# Vjtronics.net
KiCad netlist of a schematic drawn in EAGLE
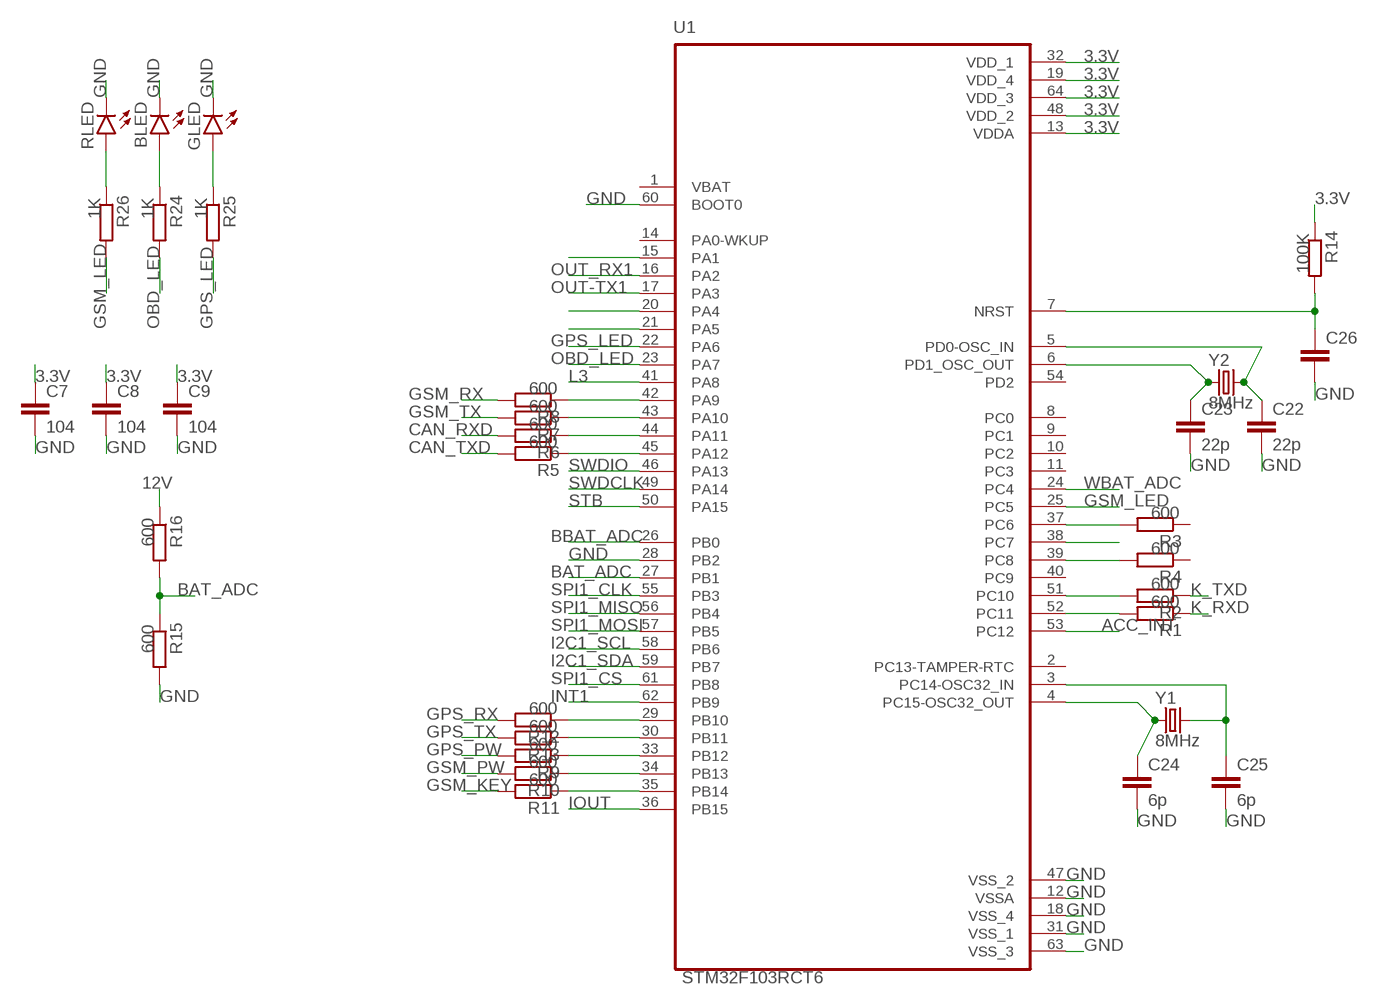
[diagram p0: schematic, sheet 1]

(export (version "E")
  (design (tool "Eeschema 10.0.6"))
  (components
    (comp (ref "BLED")
      (value "LEDCHIPLED_0805")
      (footprint "eagle-import:CHIPLED_0805")
      (libsource (lib "eagle-import") (part "LEDCHIPLED_0805"))
    )
    (comp (ref "C7")
      (value "104")
      (footprint "eagle-import:C0805")
      (libsource (lib "eagle-import") (part "C-EUC0805"))
    )
    (comp (ref "C8")
      (value "104")
      (footprint "eagle-import:C0805")
      (libsource (lib "eagle-import") (part "C-EUC0805"))
    )
    (comp (ref "C9")
      (value "104")
      (footprint "eagle-import:C0805")
      (libsource (lib "eagle-import") (part "C-EUC0805"))
    )
    (comp (ref "C22")
      (value "22p")
      (footprint "eagle-import:C0805")
      (libsource (lib "eagle-import") (part "C-EUC0805"))
    )
    (comp (ref "C23")
      (value "22p")
      (footprint "eagle-import:C0805")
      (libsource (lib "eagle-import") (part "C-EUC0805"))
    )
    (comp (ref "C24")
      (value "6p")
      (footprint "eagle-import:C0805")
      (libsource (lib "eagle-import") (part "C-EUC0805"))
    )
    (comp (ref "C25")
      (value "6p")
      (footprint "eagle-import:C0805")
      (libsource (lib "eagle-import") (part "C-EUC0805"))
    )
    (comp (ref "C26")
      (value "C-EUC0805")
      (footprint "eagle-import:C0805")
      (libsource (lib "eagle-import") (part "C-EUC0805"))
    )
    (comp (ref "GLED")
      (value "LEDCHIPLED_0805")
      (footprint "eagle-import:CHIPLED_0805")
      (libsource (lib "eagle-import") (part "LEDCHIPLED_0805"))
    )
    (comp (ref "R1")
      (value "600")
      (footprint "eagle-import:M0805")
      (libsource (lib "eagle-import") (part "R-EU_M0805"))
    )
    (comp (ref "R2")
      (value "600")
      (footprint "eagle-import:M0805")
      (libsource (lib "eagle-import") (part "R-EU_M0805"))
    )
    (comp (ref "R3")
      (value "600")
      (footprint "eagle-import:M0805")
      (libsource (lib "eagle-import") (part "R-EU_M0805"))
    )
    (comp (ref "R4")
      (value "600")
      (footprint "eagle-import:M0805")
      (libsource (lib "eagle-import") (part "R-EU_M0805"))
    )
    (comp (ref "R5")
      (value "600")
      (footprint "eagle-import:M0805")
      (libsource (lib "eagle-import") (part "R-EU_M0805"))
    )
    (comp (ref "R6")
      (value "600")
      (footprint "eagle-import:M0805")
      (libsource (lib "eagle-import") (part "R-EU_M0805"))
    )
    (comp (ref "R7")
      (value "600")
      (footprint "eagle-import:M0805")
      (libsource (lib "eagle-import") (part "R-EU_M0805"))
    )
    (comp (ref "R8")
      (value "600")
      (footprint "eagle-import:M0805")
      (libsource (lib "eagle-import") (part "R-EU_M0805"))
    )
    (comp (ref "R9")
      (value "600")
      (footprint "eagle-import:M0805")
      (libsource (lib "eagle-import") (part "R-EU_M0805"))
    )
    (comp (ref "R10")
      (value "600")
      (footprint "eagle-import:M0805")
      (libsource (lib "eagle-import") (part "R-EU_M0805"))
    )
    (comp (ref "R11")
      (value "600")
      (footprint "eagle-import:M0805")
      (libsource (lib "eagle-import") (part "R-EU_M0805"))
    )
    (comp (ref "R12")
      (value "600")
      (footprint "eagle-import:M0805")
      (libsource (lib "eagle-import") (part "R-EU_M0805"))
    )
    (comp (ref "R13")
      (value "600")
      (footprint "eagle-import:M0805")
      (libsource (lib "eagle-import") (part "R-EU_M0805"))
    )
    (comp (ref "R14")
      (value "100K")
      (footprint "eagle-import:M0805")
      (libsource (lib "eagle-import") (part "R-EU_M0805"))
    )
    (comp (ref "R15")
      (value "600")
      (footprint "eagle-import:M0805")
      (libsource (lib "eagle-import") (part "R-EU_M0805"))
    )
    (comp (ref "R16")
      (value "600")
      (footprint "eagle-import:M0805")
      (libsource (lib "eagle-import") (part "R-EU_M0805"))
    )
    (comp (ref "R24")
      (value "1K")
      (footprint "eagle-import:M0805")
      (libsource (lib "eagle-import") (part "R-EU_M0805"))
    )
    (comp (ref "R25")
      (value "1K")
      (footprint "eagle-import:M0805")
      (libsource (lib "eagle-import") (part "R-EU_M0805"))
    )
    (comp (ref "R26")
      (value "1K")
      (footprint "eagle-import:M0805")
      (libsource (lib "eagle-import") (part "R-EU_M0805"))
    )
    (comp (ref "RLED")
      (value "LEDCHIPLED_0805")
      (footprint "eagle-import:CHIPLED_0805")
      (libsource (lib "eagle-import") (part "LEDCHIPLED_0805"))
    )
    (comp (ref "U1")
      (value "STM32F103RCT6")
      (footprint "eagle-import:QFP50P1200X1200X160-64N")
      (fields (field (name "MF") "STMicroelectronics"))
      (libsource (lib "eagle-import") (part "STM32F103RCT6"))
    )
    (comp (ref "Y1")
      (value "8MHz")
      (footprint "eagle-import:CSM-7X-DU")
      (libsource (lib "eagle-import") (part "CSM-7X-DU"))
    )
    (comp (ref "Y2")
      (value "8MHz")
      (footprint "eagle-import:CSM-7X-DU")
      (libsource (lib "eagle-import") (part "CSM-7X-DU"))
    )
  )
  (nets
    (net (code "1") (name "/3.3V") (class "Default")
      (node (ref "C7") (pin "1") (pinfunction "1_1") (pintype "passive"))
      (node (ref "C8") (pin "1") (pinfunction "1_1") (pintype "passive"))
      (node (ref "C9") (pin "1") (pinfunction "1_1") (pintype "passive"))
      (node (ref "R14") (pin "1") (pinfunction "1_1") (pintype "passive"))
      (node (ref "U1") (pin "13") (pinfunction "VDDA_13") (pintype "power_in"))
      (node (ref "U1") (pin "19") (pinfunction "VDD_4_19") (pintype "power_in"))
      (node (ref "U1") (pin "32") (pinfunction "VDD_1_32") (pintype "power_in"))
      (node (ref "U1") (pin "48") (pinfunction "VDD_2_48") (pintype "power_in"))
      (node (ref "U1") (pin "64") (pinfunction "VDD_3_64") (pintype "power_in"))
    )
    (net (code "2") (name "/12V") (class "Default")
      (node (ref "R16") (pin "1") (pinfunction "1_1") (pintype "passive"))
    )
    (net (code "3") (name "/ACC_INT") (class "Default")
      (node (ref "U1") (pin "53") (pinfunction "PC12_53") (pintype "bidirectional"))
    )
    (net (code "4") (name "/BAT_ADC") (class "Default")
      (node (ref "R15") (pin "1") (pinfunction "1_1") (pintype "passive"))
      (node (ref "R16") (pin "2") (pinfunction "2_2") (pintype "passive"))
      (node (ref "U1") (pin "27") (pinfunction "PB1_27") (pintype "bidirectional"))
    )
    (net (code "5") (name "/BBAT_ADC") (class "Default")
      (node (ref "U1") (pin "26") (pinfunction "PB0_26") (pintype "bidirectional"))
    )
    (net (code "6") (name "/CAN_RXD") (class "Default")
      (node (ref "R6") (pin "2") (pinfunction "2_2") (pintype "passive"))
    )
    (net (code "7") (name "/CAN_TXD") (class "Default")
      (node (ref "R5") (pin "2") (pinfunction "2_2") (pintype "passive"))
    )
    (net (code "8") (name "/GND") (class "Default")
      (node (ref "BLED") (pin "C") (pinfunction "C_C") (pintype "passive"))
      (node (ref "C22") (pin "2") (pinfunction "2_2") (pintype "passive"))
      (node (ref "C23") (pin "2") (pinfunction "2_2") (pintype "passive"))
      (node (ref "C24") (pin "2") (pinfunction "2_2") (pintype "passive"))
      (node (ref "C25") (pin "2") (pinfunction "2_2") (pintype "passive"))
      (node (ref "C26") (pin "2") (pinfunction "2_2") (pintype "passive"))
      (node (ref "C7") (pin "2") (pinfunction "2_2") (pintype "passive"))
      (node (ref "C8") (pin "2") (pinfunction "2_2") (pintype "passive"))
      (node (ref "C9") (pin "2") (pinfunction "2_2") (pintype "passive"))
      (node (ref "GLED") (pin "C") (pinfunction "C_C") (pintype "passive"))
      (node (ref "R15") (pin "2") (pinfunction "2_2") (pintype "passive"))
      (node (ref "RLED") (pin "C") (pinfunction "C_C") (pintype "passive"))
      (node (ref "U1") (pin "12") (pinfunction "VSSA_12") (pintype "power_in"))
      (node (ref "U1") (pin "18") (pinfunction "VSS_4_18") (pintype "power_in"))
      (node (ref "U1") (pin "28") (pinfunction "PB2_28") (pintype "bidirectional"))
      (node (ref "U1") (pin "31") (pinfunction "VSS_1_31") (pintype "power_in"))
      (node (ref "U1") (pin "47") (pinfunction "VSS_2_47") (pintype "power_in"))
      (node (ref "U1") (pin "60") (pinfunction "BOOT0_60") (pintype "input"))
      (node (ref "U1") (pin "63") (pinfunction "VSS_3_63") (pintype "power_in"))
    )
    (net (code "9") (name "/GPS_LED") (class "Default")
      (node (ref "R25") (pin "2") (pinfunction "2_2") (pintype "passive"))
      (node (ref "U1") (pin "22") (pinfunction "PA6_22") (pintype "bidirectional"))
    )
    (net (code "10") (name "/GPS_PW") (class "Default")
      (node (ref "R9") (pin "2") (pinfunction "2_2") (pintype "passive"))
    )
    (net (code "11") (name "/GPS_RX") (class "Default")
      (node (ref "R12") (pin "2") (pinfunction "2_2") (pintype "passive"))
    )
    (net (code "12") (name "/GPS_TX") (class "Default")
      (node (ref "R13") (pin "2") (pinfunction "2_2") (pintype "passive"))
    )
    (net (code "13") (name "/GSM_KEY") (class "Default")
      (node (ref "R11") (pin "2") (pinfunction "2_2") (pintype "passive"))
    )
    (net (code "14") (name "/GSM_LED") (class "Default")
      (node (ref "R26") (pin "2") (pinfunction "2_2") (pintype "passive"))
      (node (ref "U1") (pin "25") (pinfunction "PC5_25") (pintype "bidirectional"))
    )
    (net (code "15") (name "/GSM_PW") (class "Default")
      (node (ref "R10") (pin "2") (pinfunction "2_2") (pintype "passive"))
    )
    (net (code "16") (name "/GSM_RX") (class "Default")
      (node (ref "R8") (pin "2") (pinfunction "2_2") (pintype "passive"))
    )
    (net (code "17") (name "/GSM_TX") (class "Default")
      (node (ref "R7") (pin "2") (pinfunction "2_2") (pintype "passive"))
    )
    (net (code "18") (name "/I2C1_SCL") (class "Default")
      (node (ref "U1") (pin "58") (pinfunction "PB6_58") (pintype "bidirectional"))
    )
    (net (code "19") (name "/I2C1_SDA") (class "Default")
      (node (ref "U1") (pin "59") (pinfunction "PB7_59") (pintype "bidirectional"))
    )
    (net (code "20") (name "/INT1") (class "Default")
      (node (ref "U1") (pin "62") (pinfunction "PB9_62") (pintype "bidirectional"))
    )
    (net (code "21") (name "/IOUT") (class "Default")
      (node (ref "U1") (pin "36") (pinfunction "PB15_36") (pintype "bidirectional"))
    )
    (net (code "22") (name "/K_RXD") (class "Default")
      (node (ref "R1") (pin "1") (pinfunction "1_1") (pintype "passive"))
    )
    (net (code "23") (name "/K_TXD") (class "Default")
      (node (ref "R2") (pin "1") (pinfunction "1_1") (pintype "passive"))
    )
    (net (code "24") (name "/L3") (class "Default")
      (node (ref "U1") (pin "41") (pinfunction "PA8_41") (pintype "bidirectional"))
    )
    (net (code "25") (name "/OBD_LED") (class "Default")
      (node (ref "R24") (pin "2") (pinfunction "2_2") (pintype "passive"))
      (node (ref "U1") (pin "23") (pinfunction "PA7_23") (pintype "bidirectional"))
    )
    (net (code "26") (name "/OUT-TX1") (class "Default")
      (node (ref "U1") (pin "17") (pinfunction "PA3_17") (pintype "bidirectional"))
    )
    (net (code "27") (name "/OUT_RX1") (class "Default")
      (node (ref "U1") (pin "16") (pinfunction "PA2_16") (pintype "bidirectional"))
    )
    (net (code "28") (name "/SPI1_CLK") (class "Default")
      (node (ref "U1") (pin "55") (pinfunction "PB3_55") (pintype "bidirectional"))
    )
    (net (code "29") (name "/SPI1_CS") (class "Default")
      (node (ref "U1") (pin "61") (pinfunction "PB8_61") (pintype "bidirectional"))
    )
    (net (code "30") (name "/SPI1_MISO") (class "Default")
      (node (ref "U1") (pin "56") (pinfunction "PB4_56") (pintype "bidirectional"))
    )
    (net (code "31") (name "/SPI1_MOSI") (class "Default")
      (node (ref "U1") (pin "57") (pinfunction "PB5_57") (pintype "bidirectional"))
    )
    (net (code "32") (name "/STB") (class "Default")
      (node (ref "U1") (pin "50") (pinfunction "PA15_50") (pintype "bidirectional"))
    )
    (net (code "33") (name "/SWDCLK") (class "Default")
      (node (ref "U1") (pin "49") (pinfunction "PA14_49") (pintype "bidirectional"))
    )
    (net (code "34") (name "/SWDIO") (class "Default")
      (node (ref "U1") (pin "46") (pinfunction "PA13_46") (pintype "bidirectional"))
    )
    (net (code "35") (name "/WBAT_ADC") (class "Default")
      (node (ref "U1") (pin "24") (pinfunction "PC4_24") (pintype "bidirectional"))
    )
    (net (code "36") (name "Net-(BLED-PadA)") (class "Default")
      (node (ref "BLED") (pin "A") (pinfunction "A_A") (pintype "passive"))
      (node (ref "R24") (pin "1") (pinfunction "1_1") (pintype "passive"))
    )
    (net (code "37") (name "Net-(GLED-PadA)") (class "Default")
      (node (ref "GLED") (pin "A") (pinfunction "A_A") (pintype "passive"))
      (node (ref "R25") (pin "1") (pinfunction "1_1") (pintype "passive"))
    )
    (net (code "38") (name "Net-(R26-Pad1)") (class "Default")
      (node (ref "R26") (pin "1") (pinfunction "1_1") (pintype "passive"))
      (node (ref "RLED") (pin "A") (pinfunction "A_A") (pintype "passive"))
    )
    (net (code "39") (name "Net-(U1-NRST)") (class "Default")
      (node (ref "C26") (pin "1") (pinfunction "1_1") (pintype "passive"))
      (node (ref "R14") (pin "2") (pinfunction "2_2") (pintype "passive"))
      (node (ref "U1") (pin "7") (pinfunction "NRST_7") (pintype "input"))
    )
    (net (code "40") (name "Net-(U1-PA9)") (class "Default")
      (node (ref "R8") (pin "1") (pinfunction "1_1") (pintype "passive"))
      (node (ref "U1") (pin "42") (pinfunction "PA9_42") (pintype "bidirectional"))
    )
    (net (code "41") (name "Net-(U1-PA10)") (class "Default")
      (node (ref "R7") (pin "1") (pinfunction "1_1") (pintype "passive"))
      (node (ref "U1") (pin "43") (pinfunction "PA10_43") (pintype "bidirectional"))
    )
    (net (code "42") (name "Net-(U1-PA11)") (class "Default")
      (node (ref "R6") (pin "1") (pinfunction "1_1") (pintype "passive"))
      (node (ref "U1") (pin "44") (pinfunction "PA11_44") (pintype "bidirectional"))
    )
    (net (code "43") (name "Net-(U1-PA12)") (class "Default")
      (node (ref "R5") (pin "1") (pinfunction "1_1") (pintype "passive"))
      (node (ref "U1") (pin "45") (pinfunction "PA12_45") (pintype "bidirectional"))
    )
    (net (code "44") (name "Net-(U1-PB10)") (class "Default")
      (node (ref "R12") (pin "1") (pinfunction "1_1") (pintype "passive"))
      (node (ref "U1") (pin "29") (pinfunction "PB10_29") (pintype "bidirectional"))
    )
    (net (code "45") (name "Net-(U1-PB11)") (class "Default")
      (node (ref "R13") (pin "1") (pinfunction "1_1") (pintype "passive"))
      (node (ref "U1") (pin "30") (pinfunction "PB11_30") (pintype "bidirectional"))
    )
    (net (code "46") (name "Net-(U1-PB12)") (class "Default")
      (node (ref "R9") (pin "1") (pinfunction "1_1") (pintype "passive"))
      (node (ref "U1") (pin "33") (pinfunction "PB12_33") (pintype "bidirectional"))
    )
    (net (code "47") (name "Net-(U1-PB13)") (class "Default")
      (node (ref "R10") (pin "1") (pinfunction "1_1") (pintype "passive"))
      (node (ref "U1") (pin "34") (pinfunction "PB13_34") (pintype "bidirectional"))
    )
    (net (code "48") (name "Net-(U1-PB14)") (class "Default")
      (node (ref "R11") (pin "1") (pinfunction "1_1") (pintype "passive"))
      (node (ref "U1") (pin "35") (pinfunction "PB14_35") (pintype "bidirectional"))
    )
    (net (code "49") (name "Net-(U1-PC6)") (class "Default")
      (node (ref "R3") (pin "2") (pinfunction "2_2") (pintype "passive"))
      (node (ref "U1") (pin "37") (pinfunction "PC6_37") (pintype "bidirectional"))
    )
    (net (code "50") (name "Net-(U1-PC8)") (class "Default")
      (node (ref "R4") (pin "2") (pinfunction "2_2") (pintype "passive"))
      (node (ref "U1") (pin "39") (pinfunction "PC8_39") (pintype "bidirectional"))
    )
    (net (code "51") (name "Net-(U1-PC10)") (class "Default")
      (node (ref "R2") (pin "2") (pinfunction "2_2") (pintype "passive"))
      (node (ref "U1") (pin "51") (pinfunction "PC10_51") (pintype "bidirectional"))
    )
    (net (code "52") (name "Net-(U1-PC11)") (class "Default")
      (node (ref "R1") (pin "2") (pinfunction "2_2") (pintype "passive"))
      (node (ref "U1") (pin "52") (pinfunction "PC11_52") (pintype "bidirectional"))
    )
    (net (code "53") (name "Net-(U1-PC14-OSC32_IN)") (class "Default")
      (node (ref "C25") (pin "1") (pinfunction "1_1") (pintype "passive"))
      (node (ref "U1") (pin "3") (pinfunction "PC14-OSC32_IN_3") (pintype "bidirectional"))
      (node (ref "Y1") (pin "2") (pinfunction "2_2") (pintype "passive"))
    )
    (net (code "54") (name "Net-(U1-PC15-OSC32_OUT)") (class "Default")
      (node (ref "C24") (pin "1") (pinfunction "1_1") (pintype "passive"))
      (node (ref "U1") (pin "4") (pinfunction "PC15-OSC32_OUT_4") (pintype "bidirectional"))
      (node (ref "Y1") (pin "1") (pinfunction "1_1") (pintype "passive"))
    )
    (net (code "55") (name "Net-(U1-PD0-OSC_IN)") (class "Default")
      (node (ref "C22") (pin "1") (pinfunction "1_1") (pintype "passive"))
      (node (ref "U1") (pin "5") (pinfunction "PD0-OSC_IN_5") (pintype "input"))
      (node (ref "Y2") (pin "2") (pinfunction "2_2") (pintype "passive"))
    )
    (net (code "56") (name "Net-(U1-PD1_OSC_OUT)") (class "Default")
      (node (ref "C23") (pin "1") (pinfunction "1_1") (pintype "passive"))
      (node (ref "U1") (pin "6") (pinfunction "PD1_OSC_OUT_6") (pintype "output"))
      (node (ref "Y2") (pin "1") (pinfunction "1_1") (pintype "passive"))
    )
    (net (code "57") (name "unconnected-(R3-Pad1)") (class "Default")
      (node (ref "R3") (pin "1") (pinfunction "1_1") (pintype "passive"))
    )
    (net (code "58") (name "unconnected-(R4-Pad1)") (class "Default")
      (node (ref "R4") (pin "1") (pinfunction "1_1") (pintype "passive"))
    )
    (net (code "59") (name "unconnected-(U1-PA0-WKUP-Pad14)") (class "Default")
      (node (ref "U1") (pin "14") (pinfunction "PA0-WKUP_14") (pintype "bidirectional"))
    )
    (net (code "60") (name "unconnected-(U1-PA1-Pad15)") (class "Default")
      (node (ref "U1") (pin "15") (pinfunction "PA1_15") (pintype "bidirectional"))
    )
    (net (code "61") (name "unconnected-(U1-PA4-Pad20)") (class "Default")
      (node (ref "U1") (pin "20") (pinfunction "PA4_20") (pintype "bidirectional"))
    )
    (net (code "62") (name "unconnected-(U1-PA5-Pad21)") (class "Default")
      (node (ref "U1") (pin "21") (pinfunction "PA5_21") (pintype "bidirectional"))
    )
    (net (code "63") (name "unconnected-(U1-PC0-Pad8)") (class "Default")
      (node (ref "U1") (pin "8") (pinfunction "PC0_8") (pintype "bidirectional"))
    )
    (net (code "64") (name "unconnected-(U1-PC1-Pad9)") (class "Default")
      (node (ref "U1") (pin "9") (pinfunction "PC1_9") (pintype "bidirectional"))
    )
    (net (code "65") (name "unconnected-(U1-PC2-Pad10)") (class "Default")
      (node (ref "U1") (pin "10") (pinfunction "PC2_10") (pintype "bidirectional"))
    )
    (net (code "66") (name "unconnected-(U1-PC3-Pad11)") (class "Default")
      (node (ref "U1") (pin "11") (pinfunction "PC3_11") (pintype "bidirectional"))
    )
    (net (code "67") (name "unconnected-(U1-PC7-Pad38)") (class "Default")
      (node (ref "U1") (pin "38") (pinfunction "PC7_38") (pintype "bidirectional"))
    )
    (net (code "68") (name "unconnected-(U1-PC9-Pad40)") (class "Default")
      (node (ref "U1") (pin "40") (pinfunction "PC9_40") (pintype "bidirectional"))
    )
    (net (code "69") (name "unconnected-(U1-PC13-TAMPER-RTC-Pad2)") (class "Default")
      (node (ref "U1") (pin "2") (pinfunction "PC13-TAMPER-RTC_2") (pintype "bidirectional"))
    )
    (net (code "70") (name "unconnected-(U1-PD2-Pad54)") (class "Default")
      (node (ref "U1") (pin "54") (pinfunction "PD2_54") (pintype "bidirectional"))
    )
    (net (code "71") (name "unconnected-(U1-VBAT-Pad1)") (class "Default")
      (node (ref "U1") (pin "1") (pinfunction "VBAT_1") (pintype "input"))
    )
  )
)
